# USBasp.net
KiCad netlist of a schematic drawn in EAGLE
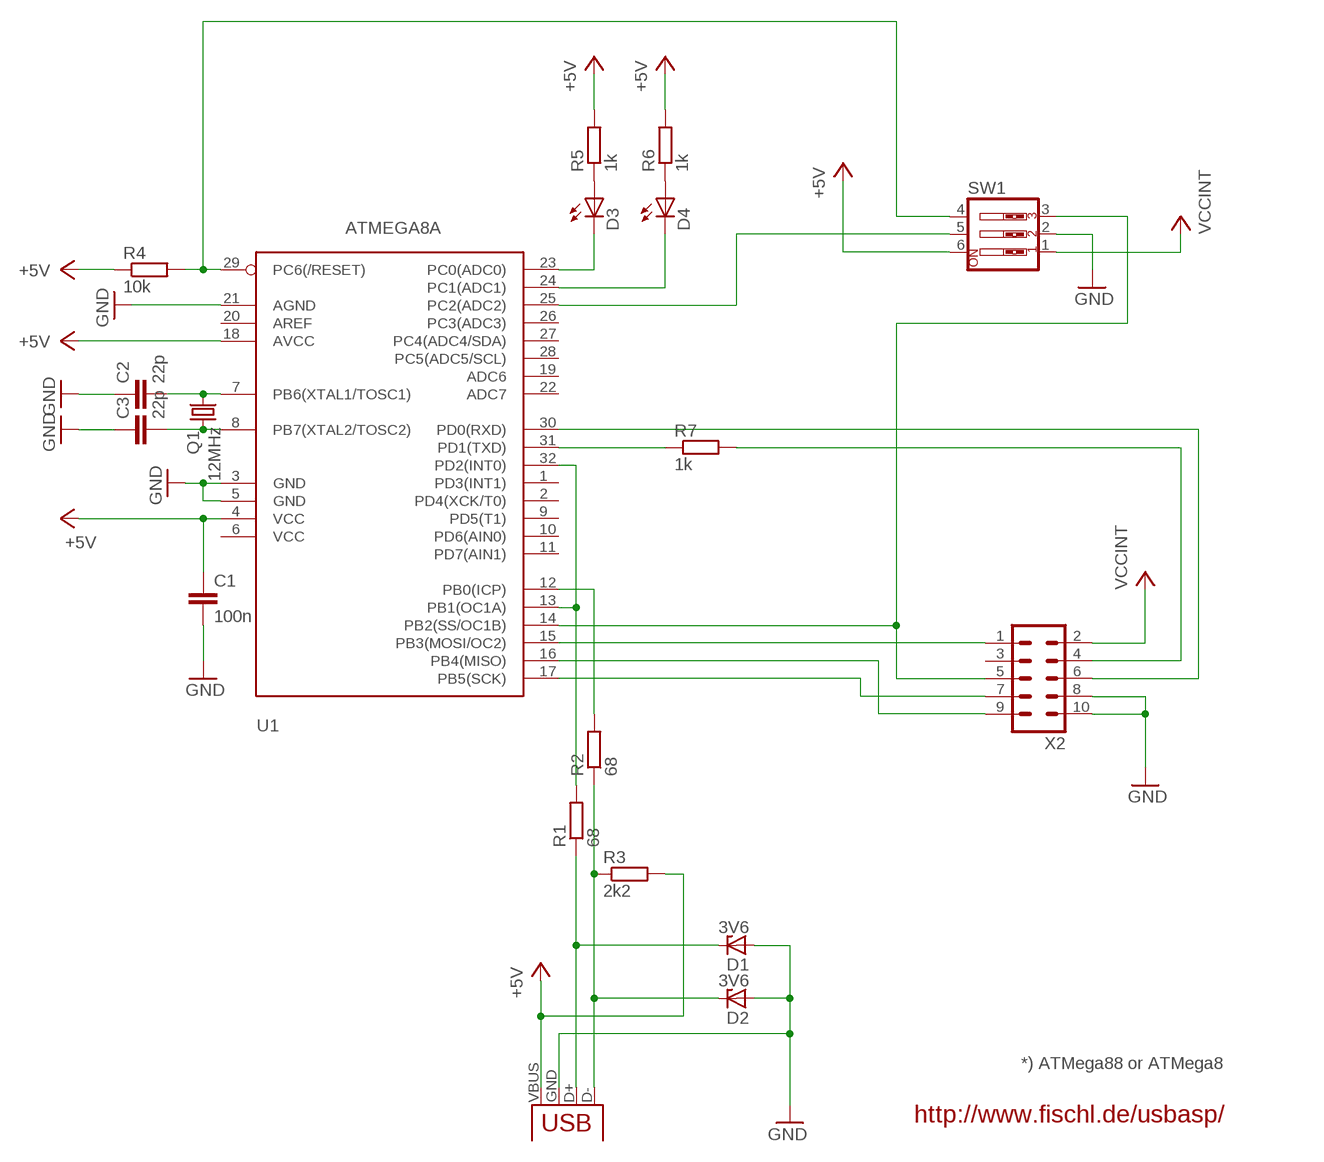
[diagram p0: schematic, sheet 1]

(export (version "E")
  (design (tool "Eeschema 10.0.6"))
  (components
    (comp (ref "C1")
      (value "100n")
      (footprint "eagle-import:C0805")
      (libsource (lib "eagle-import") (part "C-EUC0805"))
    )
    (comp (ref "C2")
      (value "22p")
      (footprint "eagle-import:C0805")
      (libsource (lib "eagle-import") (part "C-EUC0805"))
    )
    (comp (ref "C3")
      (value "22p")
      (footprint "eagle-import:C0805")
      (libsource (lib "eagle-import") (part "C-EUC0805"))
    )
    (comp (ref "D1")
      (value "3V6")
      (footprint "eagle-import:SOD80C")
      (libsource (lib "eagle-import") (part "ZENER-DIODESOD80C"))
    )
    (comp (ref "D2")
      (value "3V6")
      (footprint "eagle-import:SOD80C")
      (libsource (lib "eagle-import") (part "ZENER-DIODESOD80C"))
    )
    (comp (ref "D3")
      (value "LEDCHIPLED_0805")
      (footprint "eagle-import:CHIPLED_0805")
      (libsource (lib "eagle-import") (part "LEDCHIPLED_0805"))
    )
    (comp (ref "D4")
      (value "LEDCHIPLED_0805")
      (footprint "eagle-import:CHIPLED_0805")
      (libsource (lib "eagle-import") (part "LEDCHIPLED_0805"))
    )
    (comp (ref "Q1")
      (value "12MHz")
      (footprint "eagle-import:HC49_S")
      (libsource (lib "eagle-import") (part "CRYTALHC49S"))
    )
    (comp (ref "R1")
      (value "68")
      (footprint "eagle-import:R0805")
      (libsource (lib "eagle-import") (part "R-EU_R0805"))
    )
    (comp (ref "R2")
      (value "68")
      (footprint "eagle-import:R0805")
      (libsource (lib "eagle-import") (part "R-EU_R0805"))
    )
    (comp (ref "R3")
      (value "2k2")
      (footprint "eagle-import:R0805")
      (libsource (lib "eagle-import") (part "R-EU_R0805"))
    )
    (comp (ref "R4")
      (value "10k")
      (footprint "eagle-import:R0805")
      (libsource (lib "eagle-import") (part "R-EU_R0805"))
    )
    (comp (ref "R5")
      (value "1k")
      (footprint "eagle-import:R0805")
      (libsource (lib "eagle-import") (part "R-EU_R0805"))
    )
    (comp (ref "R6")
      (value "1k")
      (footprint "eagle-import:R0805")
      (libsource (lib "eagle-import") (part "R-EU_R0805"))
    )
    (comp (ref "R7")
      (value "1k")
      (footprint "eagle-import:R0805")
      (libsource (lib "eagle-import") (part "R-EU_R0805"))
    )
    (comp (ref "SW1")
      (value "SW_DIP-3")
      (footprint "eagle-import:EDG-03")
      (libsource (lib "eagle-import") (part "SW_DIP-3"))
    )
    (comp (ref "U1")
      (value "ATMEGA8A")
      (footprint "eagle-import:TQFP32-08")
      (libsource (lib "eagle-import") (part "AVR-MEGA8-AI"))
    )
    (comp (ref "X1")
      (value "USB-A-H")
      (footprint "eagle-import:USB-A-H")
      (libsource (lib "eagle-import") (part "USB-A-H"))
    )
    (comp (ref "X2")
      (value "ML10L")
      (footprint "eagle-import:ML10L")
      (libsource (lib "eagle-import") (part "ML10L"))
    )
  )
  (nets
    (net (code "1") (name "+5V") (class "Default")
      (node (ref "C1") (pin "1") (pinfunction "1_1") (pintype "passive"))
      (node (ref "R3") (pin "2") (pinfunction "2_2") (pintype "passive"))
      (node (ref "R4") (pin "1") (pinfunction "1_1") (pintype "passive"))
      (node (ref "R5") (pin "2") (pinfunction "2_2") (pintype "passive"))
      (node (ref "R6") (pin "2") (pinfunction "2_2") (pintype "passive"))
      (node (ref "SW1") (pin "6") (pinfunction "6_6") (pintype "passive"))
      (node (ref "U1") (pin "18") (pinfunction "AVCC_18") (pintype "bidirectional"))
      (node (ref "U1") (pin "4") (pinfunction "VCC_4") (pintype "bidirectional"))
      (node (ref "X1") (pin "VBUS") (pinfunction "GND_VBUS") (pintype "bidirectional"))
    )
    (net (code "2") (name "GND") (class "Default")
      (node (ref "C1") (pin "2") (pinfunction "2_2") (pintype "passive"))
      (node (ref "C2") (pin "1") (pinfunction "1_1") (pintype "passive"))
      (node (ref "C3") (pin "1") (pinfunction "1_1") (pintype "passive"))
      (node (ref "D1") (pin "A") (pinfunction "A_A") (pintype "passive"))
      (node (ref "D2") (pin "A") (pinfunction "A_A") (pintype "passive"))
      (node (ref "SW1") (pin "2") (pinfunction "2_2") (pintype "passive"))
      (node (ref "U1") (pin "21") (pinfunction "AGND_21") (pintype "bidirectional"))
      (node (ref "U1") (pin "3") (pinfunction "GND_3") (pintype "bidirectional"))
      (node (ref "U1") (pin "5") (pinfunction "GND_5") (pintype "bidirectional"))
      (node (ref "X1") (pin "GND") (pinfunction "VBUS_GND") (pintype "bidirectional"))
      (node (ref "X2") (pin "10") (pinfunction "10_10") (pintype "passive"))
      (node (ref "X2") (pin "8") (pinfunction "8_8") (pintype "passive"))
    )
    (net (code "3") (name "Net-(D3-PadA)") (class "Default")
      (node (ref "D3") (pin "A") (pinfunction "A_A") (pintype "passive"))
      (node (ref "R5") (pin "1") (pinfunction "1_1") (pintype "passive"))
    )
    (net (code "4") (name "Net-(D4-PadA)") (class "Default")
      (node (ref "D4") (pin "A") (pinfunction "A_A") (pintype "passive"))
      (node (ref "R6") (pin "1") (pinfunction "1_1") (pintype "passive"))
    )
    (net (code "5") (name "Net-(R7-Pad2)") (class "Default")
      (node (ref "R7") (pin "2") (pinfunction "2_2") (pintype "passive"))
      (node (ref "X2") (pin "4") (pinfunction "4_4") (pintype "passive"))
    )
    (net (code "6") (name "Net-(U1-PB0(ICP))") (class "Default")
      (node (ref "R2") (pin "2") (pinfunction "2_2") (pintype "passive"))
      (node (ref "U1") (pin "12") (pinfunction "PB0(ICP)_12") (pintype "bidirectional"))
    )
    (net (code "7") (name "Net-(U1-PB1(OC1A))") (class "Default")
      (node (ref "R1") (pin "2") (pinfunction "2_2") (pintype "passive"))
      (node (ref "U1") (pin "13") (pinfunction "PB1(OC1A)_13") (pintype "bidirectional"))
      (node (ref "U1") (pin "32") (pinfunction "PD2(INT0)_32") (pintype "bidirectional"))
    )
    (net (code "8") (name "Net-(U1-PB2(SS{slash}OC1B))") (class "Default")
      (node (ref "SW1") (pin "3") (pinfunction "3_3") (pintype "passive"))
      (node (ref "U1") (pin "14") (pinfunction "PB2(SS/OC1B)_14") (pintype "bidirectional"))
      (node (ref "X2") (pin "5") (pinfunction "5_5") (pintype "passive"))
    )
    (net (code "9") (name "Net-(U1-PB3(MOSI{slash}OC2))") (class "Default")
      (node (ref "U1") (pin "15") (pinfunction "PB3(MOSI/OC2)_15") (pintype "bidirectional"))
      (node (ref "X2") (pin "1") (pinfunction "1_1") (pintype "passive"))
    )
    (net (code "10") (name "Net-(U1-PB4(MISO))") (class "Default")
      (node (ref "U1") (pin "16") (pinfunction "PB4(MISO)_16") (pintype "bidirectional"))
      (node (ref "X2") (pin "9") (pinfunction "9_9") (pintype "passive"))
    )
    (net (code "11") (name "Net-(U1-PB5(SCK))") (class "Default")
      (node (ref "U1") (pin "17") (pinfunction "PB5(SCK)_17") (pintype "bidirectional"))
      (node (ref "X2") (pin "7") (pinfunction "7_7") (pintype "passive"))
    )
    (net (code "12") (name "Net-(U1-PB6(XTAL1{slash}TOSC1))") (class "Default")
      (node (ref "C2") (pin "2") (pinfunction "2_2") (pintype "passive"))
      (node (ref "Q1") (pin "2") (pinfunction "2_2") (pintype "passive"))
      (node (ref "U1") (pin "7") (pinfunction "PB6(XTAL1/TOSC1)_7") (pintype "bidirectional"))
    )
    (net (code "13") (name "Net-(U1-PB7(XTAL2{slash}TOSC2))") (class "Default")
      (node (ref "C3") (pin "2") (pinfunction "2_2") (pintype "passive"))
      (node (ref "Q1") (pin "1") (pinfunction "1_1") (pintype "passive"))
      (node (ref "U1") (pin "8") (pinfunction "PB7(XTAL2/TOSC2)_8") (pintype "bidirectional"))
    )
    (net (code "14") (name "Net-(U1-PC0(ADC0))") (class "Default")
      (node (ref "D3") (pin "C") (pinfunction "C_C") (pintype "passive"))
      (node (ref "U1") (pin "23") (pinfunction "PC0(ADC0)_23") (pintype "bidirectional"))
    )
    (net (code "15") (name "Net-(U1-PC1(ADC1))") (class "Default")
      (node (ref "D4") (pin "C") (pinfunction "C_C") (pintype "passive"))
      (node (ref "U1") (pin "24") (pinfunction "PC1(ADC1)_24") (pintype "bidirectional"))
    )
    (net (code "16") (name "Net-(U1-PC2(ADC2))") (class "Default")
      (node (ref "SW1") (pin "5") (pinfunction "5_5") (pintype "passive"))
      (node (ref "U1") (pin "25") (pinfunction "PC2(ADC2)_25") (pintype "bidirectional"))
    )
    (net (code "17") (name "Net-(U1-PC6({slash}RESET))") (class "Default")
      (node (ref "R4") (pin "2") (pinfunction "2_2") (pintype "passive"))
      (node (ref "SW1") (pin "4") (pinfunction "4_4") (pintype "passive"))
      (node (ref "U1") (pin "29") (pinfunction "PC6(/RESET)_29") (pintype "bidirectional"))
    )
    (net (code "18") (name "Net-(U1-PD0(RXD))") (class "Default")
      (node (ref "U1") (pin "30") (pinfunction "PD0(RXD)_30") (pintype "bidirectional"))
      (node (ref "X2") (pin "6") (pinfunction "6_6") (pintype "passive"))
    )
    (net (code "19") (name "Net-(U1-PD1(TXD))") (class "Default")
      (node (ref "R7") (pin "1") (pinfunction "1_1") (pintype "passive"))
      (node (ref "U1") (pin "31") (pinfunction "PD1(TXD)_31") (pintype "bidirectional"))
    )
    (net (code "20") (name "Net-(X1-D+)") (class "Default")
      (node (ref "D2") (pin "C") (pinfunction "C_C") (pintype "passive"))
      (node (ref "R2") (pin "1") (pinfunction "1_1") (pintype "passive"))
      (node (ref "R3") (pin "1") (pinfunction "1_1") (pintype "passive"))
      (node (ref "X1") (pin "D-") (pinfunction "D+_D-") (pintype "bidirectional"))
    )
    (net (code "21") (name "Net-(X1-D-)") (class "Default")
      (node (ref "D1") (pin "C") (pinfunction "C_C") (pintype "passive"))
      (node (ref "R1") (pin "1") (pinfunction "1_1") (pintype "passive"))
      (node (ref "X1") (pin "D+") (pinfunction "D-_D+") (pintype "bidirectional"))
    )
    (net (code "22") (name "VCCINT") (class "Default")
      (node (ref "SW1") (pin "1") (pinfunction "1_1") (pintype "passive"))
      (node (ref "X2") (pin "2") (pinfunction "2_2") (pintype "passive"))
    )
    (net (code "23") (name "unconnected-(U1-ADC6-Pad19)") (class "Default")
      (node (ref "U1") (pin "19") (pinfunction "ADC6_19") (pintype "bidirectional"))
    )
    (net (code "24") (name "unconnected-(U1-ADC7-Pad22)") (class "Default")
      (node (ref "U1") (pin "22") (pinfunction "ADC7_22") (pintype "bidirectional"))
    )
    (net (code "25") (name "unconnected-(U1-AREF-Pad20)") (class "Default")
      (node (ref "U1") (pin "20") (pinfunction "AREF_20") (pintype "bidirectional"))
    )
    (net (code "26") (name "unconnected-(U1-PC3(ADC3)-Pad26)") (class "Default")
      (node (ref "U1") (pin "26") (pinfunction "PC3(ADC3)_26") (pintype "bidirectional"))
    )
    (net (code "27") (name "unconnected-(U1-PC4(ADC4{slash}SDA)-Pad27)") (class "Default")
      (node (ref "U1") (pin "27") (pinfunction "PC4(ADC4/SDA)_27") (pintype "bidirectional"))
    )
    (net (code "28") (name "unconnected-(U1-PC5(ADC5{slash}SCL)-Pad28)") (class "Default")
      (node (ref "U1") (pin "28") (pinfunction "PC5(ADC5/SCL)_28") (pintype "bidirectional"))
    )
    (net (code "29") (name "unconnected-(U1-PD3(INT1)-Pad1)") (class "Default")
      (node (ref "U1") (pin "1") (pinfunction "PD3(INT1)_1") (pintype "bidirectional"))
    )
    (net (code "30") (name "unconnected-(U1-PD4(XCK{slash}T0)-Pad2)") (class "Default")
      (node (ref "U1") (pin "2") (pinfunction "PD4(XCK/T0)_2") (pintype "bidirectional"))
    )
    (net (code "31") (name "unconnected-(U1-PD5(T1)-Pad9)") (class "Default")
      (node (ref "U1") (pin "9") (pinfunction "PD5(T1)_9") (pintype "bidirectional"))
    )
    (net (code "32") (name "unconnected-(U1-PD6(AIN0)-Pad10)") (class "Default")
      (node (ref "U1") (pin "10") (pinfunction "PD6(AIN0)_10") (pintype "bidirectional"))
    )
    (net (code "33") (name "unconnected-(U1-PD7(AIN1)-Pad11)") (class "Default")
      (node (ref "U1") (pin "11") (pinfunction "PD7(AIN1)_11") (pintype "bidirectional"))
    )
    (net (code "34") (name "unconnected-(U1-VCC-Pad6)") (class "Default")
      (node (ref "U1") (pin "6") (pinfunction "VCC_6") (pintype "bidirectional"))
    )
    (net (code "35") (name "unconnected-(X2-Pad3)") (class "Default")
      (node (ref "X2") (pin "3") (pinfunction "3_3") (pintype "passive"))
    )
  )
)
